# KIM_6530_replacement.net
KiCad netlist of a schematic drawn in EAGLE
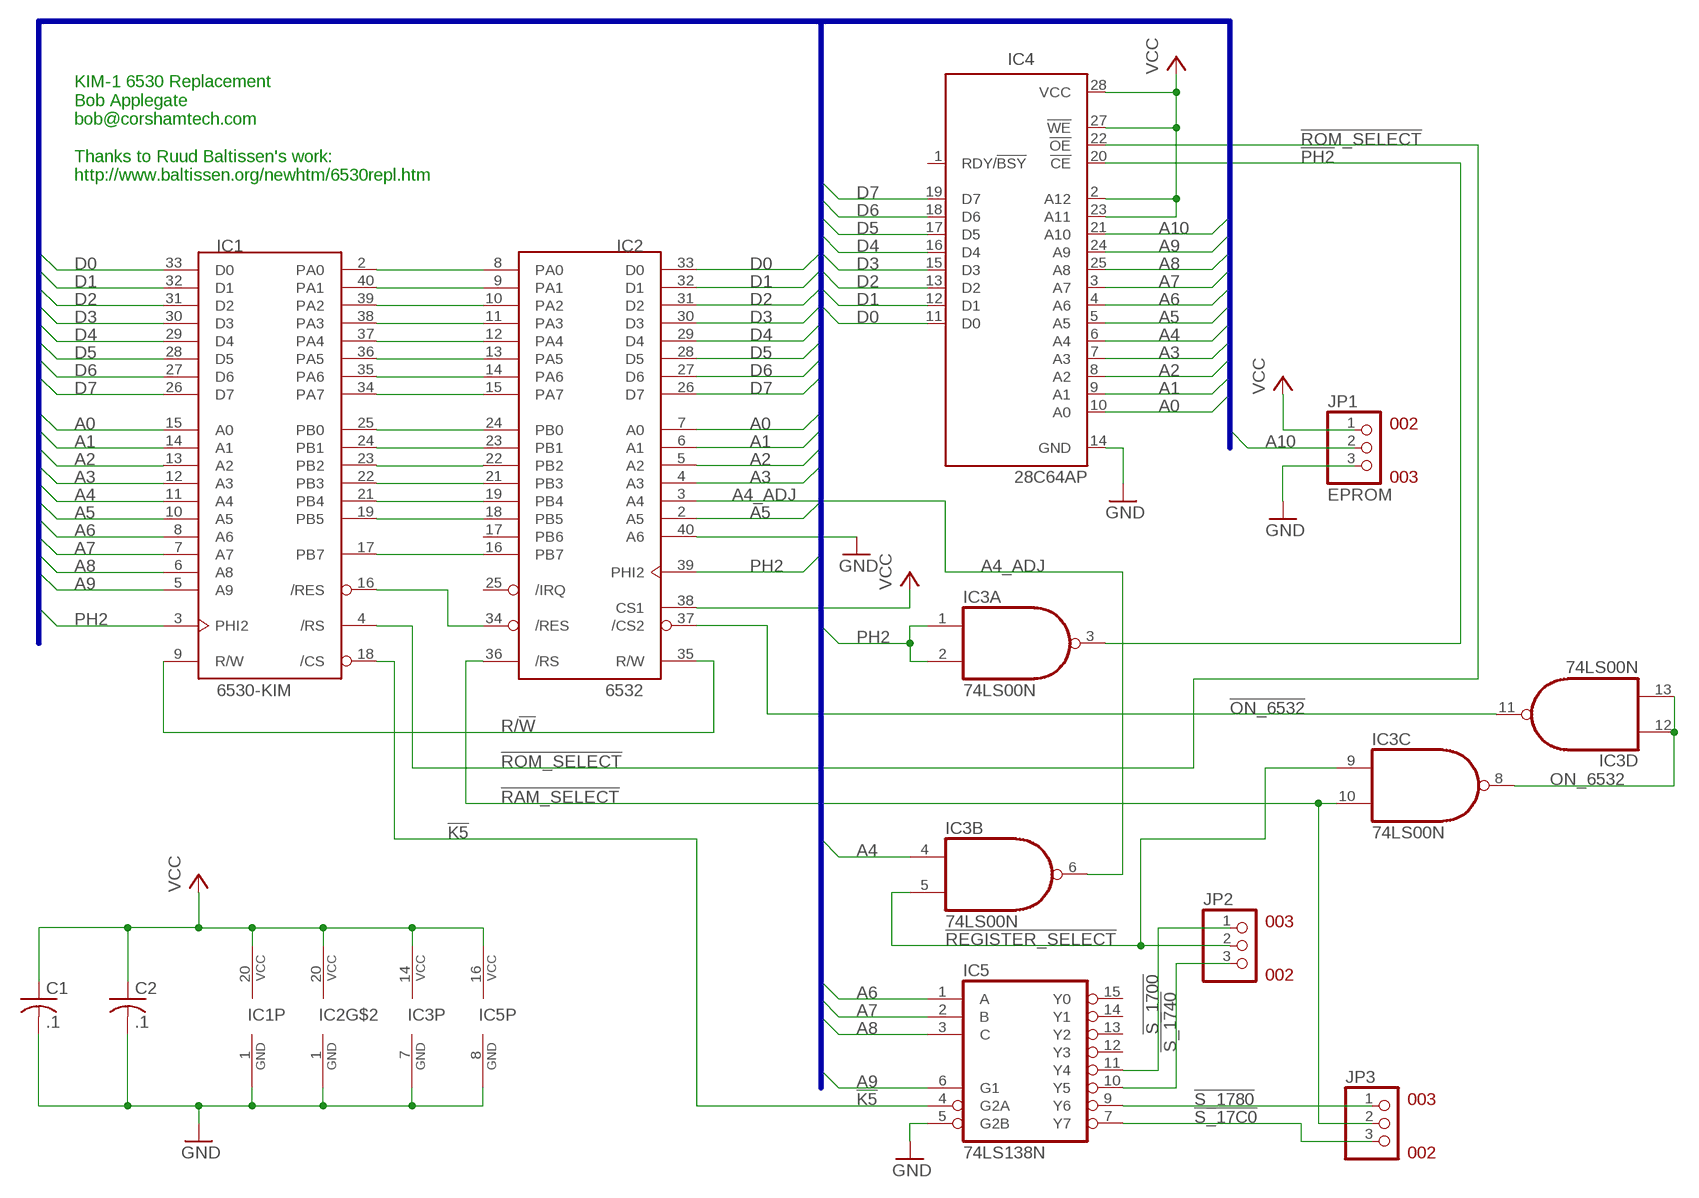
[diagram p0: schematic, sheet 1]

(export (version "E")
  (design (tool "Eeschema 10.0.6"))
  (components
    (comp (ref "C1")
      (value ".1")
      (footprint "eagle-import:C025-025X050")
      (libsource (lib "eagle-import") (part "C-US025-025X050"))
    )
    (comp (ref "C2")
      (value ".1")
      (footprint "eagle-import:C025-025X050")
      (libsource (lib "eagle-import") (part "C-US025-025X050"))
    )
    (comp (ref "IC1")
      (value "6530-KIM")
      (footprint "eagle-import:DIP40")
      (libsource (lib "eagle-import") (part "6530-KIM"))
    )
    (comp (ref "IC2")
      (value "6532")
      (footprint "eagle-import:DIP40")
      (libsource (lib "eagle-import") (part "6532"))
    )
    (comp (ref "IC3")
      (value "74LS00N")
      (footprint "eagle-import:DIL14")
      (libsource (lib "eagle-import") (part "7400NLS"))
    )
    (comp (ref "IC4")
      (value "28C64AP")
      (footprint "eagle-import:DIL28-6")
      (fields (field (name "MPN") "AT28C64B-15PU"))
      (libsource (lib "eagle-import") (part "2864APC"))
    )
    (comp (ref "IC5")
      (value "74LS138N")
      (footprint "eagle-import:DIL16")
      (libsource (lib "eagle-import") (part "74138NLS"))
    )
    (comp (ref "JP1")
      (value "EPROM")
      (footprint "eagle-import:1X03")
      (libsource (lib "eagle-import") (part "PINHD-1X3"))
    )
    (comp (ref "JP2")
      (value "PINHD-1X3")
      (footprint "eagle-import:1X03")
      (libsource (lib "eagle-import") (part "PINHD-1X3"))
    )
    (comp (ref "JP3")
      (value "PINHD-1X3")
      (footprint "eagle-import:1X03")
      (libsource (lib "eagle-import") (part "PINHD-1X3"))
    )
  )
  (nets
    (net (code "1") (name "/A0") (class "Default")
      (node (ref "IC1") (pin "15") (pinfunction "A0_15") (pintype "input"))
      (node (ref "IC2") (pin "7") (pinfunction "A0_7") (pintype "input"))
      (node (ref "IC4") (pin "10") (pinfunction "A0_10") (pintype "input"))
    )
    (net (code "2") (name "/A1") (class "Default")
      (node (ref "IC1") (pin "14") (pinfunction "A1_14") (pintype "input"))
      (node (ref "IC2") (pin "6") (pinfunction "A1_6") (pintype "input"))
      (node (ref "IC4") (pin "9") (pinfunction "A1_9") (pintype "input"))
    )
    (net (code "3") (name "/A2") (class "Default")
      (node (ref "IC1") (pin "13") (pinfunction "A2_13") (pintype "input"))
      (node (ref "IC2") (pin "5") (pinfunction "A2_5") (pintype "input"))
      (node (ref "IC4") (pin "8") (pinfunction "A2_8") (pintype "input"))
    )
    (net (code "4") (name "/A3") (class "Default")
      (node (ref "IC1") (pin "12") (pinfunction "A3_12") (pintype "input"))
      (node (ref "IC2") (pin "4") (pinfunction "A3_4") (pintype "input"))
      (node (ref "IC4") (pin "7") (pinfunction "A3_7") (pintype "input"))
    )
    (net (code "5") (name "/A4") (class "Default")
      (node (ref "IC1") (pin "11") (pinfunction "A4_11") (pintype "input"))
      (node (ref "IC3") (pin "4") (pinfunction "I0_4") (pintype "input"))
      (node (ref "IC4") (pin "6") (pinfunction "A4_6") (pintype "input"))
    )
    (net (code "6") (name "/A4_ADJ") (class "Default")
      (node (ref "IC2") (pin "3") (pinfunction "A4_3") (pintype "input"))
      (node (ref "IC3") (pin "6") (pinfunction "O_6") (pintype "output"))
    )
    (net (code "7") (name "/A5") (class "Default")
      (node (ref "IC1") (pin "10") (pinfunction "A5_10") (pintype "input"))
      (node (ref "IC2") (pin "2") (pinfunction "A5_2") (pintype "input"))
      (node (ref "IC4") (pin "5") (pinfunction "A5_5") (pintype "input"))
    )
    (net (code "8") (name "/A6") (class "Default")
      (node (ref "IC1") (pin "8") (pinfunction "A6_8") (pintype "input"))
      (node (ref "IC4") (pin "4") (pinfunction "A6_4") (pintype "input"))
      (node (ref "IC5") (pin "1") (pinfunction "A_1") (pintype "input"))
    )
    (net (code "9") (name "/A7") (class "Default")
      (node (ref "IC1") (pin "7") (pinfunction "A7_7") (pintype "input"))
      (node (ref "IC4") (pin "3") (pinfunction "A7_3") (pintype "input"))
      (node (ref "IC5") (pin "2") (pinfunction "B_2") (pintype "input"))
    )
    (net (code "10") (name "/A8") (class "Default")
      (node (ref "IC1") (pin "6") (pinfunction "A8_6") (pintype "input"))
      (node (ref "IC4") (pin "25") (pinfunction "A8_25") (pintype "input"))
      (node (ref "IC5") (pin "3") (pinfunction "C_3") (pintype "input"))
    )
    (net (code "11") (name "/A9") (class "Default")
      (node (ref "IC1") (pin "5") (pinfunction "A9_5") (pintype "input"))
      (node (ref "IC4") (pin "24") (pinfunction "A9_24") (pintype "input"))
      (node (ref "IC5") (pin "6") (pinfunction "G1_6") (pintype "input"))
    )
    (net (code "12") (name "/A10") (class "Default")
      (node (ref "IC4") (pin "21") (pinfunction "A10_21") (pintype "input"))
      (node (ref "JP1") (pin "2") (pinfunction "2_2") (pintype "passive"))
    )
    (net (code "13") (name "/D0") (class "Default")
      (node (ref "IC1") (pin "33") (pinfunction "D0_33") (pintype "bidirectional"))
      (node (ref "IC2") (pin "33") (pinfunction "D0_33") (pintype "bidirectional"))
      (node (ref "IC4") (pin "11") (pinfunction "D0_11") (pintype "tri_state"))
    )
    (net (code "14") (name "/D1") (class "Default")
      (node (ref "IC1") (pin "32") (pinfunction "D1_32") (pintype "bidirectional"))
      (node (ref "IC2") (pin "32") (pinfunction "D1_32") (pintype "bidirectional"))
      (node (ref "IC4") (pin "12") (pinfunction "D1_12") (pintype "tri_state"))
    )
    (net (code "15") (name "/D2") (class "Default")
      (node (ref "IC1") (pin "31") (pinfunction "D2_31") (pintype "bidirectional"))
      (node (ref "IC2") (pin "31") (pinfunction "D2_31") (pintype "bidirectional"))
      (node (ref "IC4") (pin "13") (pinfunction "D2_13") (pintype "tri_state"))
    )
    (net (code "16") (name "/D3") (class "Default")
      (node (ref "IC1") (pin "30") (pinfunction "D3_30") (pintype "bidirectional"))
      (node (ref "IC2") (pin "30") (pinfunction "D3_30") (pintype "bidirectional"))
      (node (ref "IC4") (pin "15") (pinfunction "D3_15") (pintype "tri_state"))
    )
    (net (code "17") (name "/D4") (class "Default")
      (node (ref "IC1") (pin "29") (pinfunction "D4_29") (pintype "bidirectional"))
      (node (ref "IC2") (pin "29") (pinfunction "D4_29") (pintype "bidirectional"))
      (node (ref "IC4") (pin "16") (pinfunction "D4_16") (pintype "tri_state"))
    )
    (net (code "18") (name "/D5") (class "Default")
      (node (ref "IC1") (pin "28") (pinfunction "D5_28") (pintype "bidirectional"))
      (node (ref "IC2") (pin "28") (pinfunction "D5_28") (pintype "bidirectional"))
      (node (ref "IC4") (pin "17") (pinfunction "D5_17") (pintype "tri_state"))
    )
    (net (code "19") (name "/D6") (class "Default")
      (node (ref "IC1") (pin "27") (pinfunction "D6_27") (pintype "bidirectional"))
      (node (ref "IC2") (pin "27") (pinfunction "D6_27") (pintype "bidirectional"))
      (node (ref "IC4") (pin "18") (pinfunction "D6_18") (pintype "tri_state"))
    )
    (net (code "20") (name "/D7") (class "Default")
      (node (ref "IC1") (pin "26") (pinfunction "D7_26") (pintype "bidirectional"))
      (node (ref "IC2") (pin "26") (pinfunction "D7_26") (pintype "bidirectional"))
      (node (ref "IC4") (pin "19") (pinfunction "D7_19") (pintype "tri_state"))
    )
    (net (code "21") (name "/ON_6532") (class "Default")
      (node (ref "IC3") (pin "12") (pinfunction "I0_12") (pintype "input"))
      (node (ref "IC3") (pin "13") (pinfunction "I1_13") (pintype "input"))
      (node (ref "IC3") (pin "8") (pinfunction "O_8") (pintype "output"))
    )
    (net (code "22") (name "/PH2") (class "Default")
      (node (ref "IC1") (pin "3") (pinfunction "PHI2_3") (pintype "input"))
      (node (ref "IC2") (pin "39") (pinfunction "PHI2_39") (pintype "input"))
      (node (ref "IC3") (pin "1") (pinfunction "I0_1") (pintype "input"))
      (node (ref "IC3") (pin "2") (pinfunction "I1_2") (pintype "input"))
    )
    (net (code "23") (name "/R{slash}~{W}") (class "Default")
      (node (ref "IC1") (pin "9") (pinfunction "R/W_9") (pintype "input"))
      (node (ref "IC2") (pin "35") (pinfunction "R/W_35") (pintype "input"))
    )
    (net (code "24") (name "/~{K5}") (class "Default")
      (node (ref "IC1") (pin "18") (pinfunction "/CS_18") (pintype "input"))
      (node (ref "IC5") (pin "4") (pinfunction "G2A_4") (pintype "input"))
    )
    (net (code "25") (name "/~{ON_6532}") (class "Default")
      (node (ref "IC2") (pin "37") (pinfunction "/CS2_37") (pintype "input"))
      (node (ref "IC3") (pin "11") (pinfunction "O_11") (pintype "output"))
    )
    (net (code "26") (name "/~{PH2}") (class "Default")
      (node (ref "IC3") (pin "3") (pinfunction "O_3") (pintype "output"))
      (node (ref "IC4") (pin "20") (pinfunction "~{CE}_20") (pintype "input"))
    )
    (net (code "27") (name "/~{RAM_SELECT}") (class "Default")
      (node (ref "IC2") (pin "36") (pinfunction "/RS_36") (pintype "input"))
      (node (ref "IC3") (pin "10") (pinfunction "I1_10") (pintype "input"))
      (node (ref "JP3") (pin "2") (pinfunction "2_2") (pintype "passive"))
    )
    (net (code "28") (name "/~{REGISTER_SELECT}") (class "Default")
      (node (ref "IC3") (pin "5") (pinfunction "I1_5") (pintype "input"))
      (node (ref "IC3") (pin "9") (pinfunction "I0_9") (pintype "input"))
      (node (ref "JP2") (pin "2") (pinfunction "2_2") (pintype "passive"))
    )
    (net (code "29") (name "/~{ROM_SELECT}") (class "Default")
      (node (ref "IC1") (pin "4") (pinfunction "/RS_4") (pintype "input"))
      (node (ref "IC4") (pin "22") (pinfunction "~{OE}_22") (pintype "input"))
    )
    (net (code "30") (name "/~{S_17C0}") (class "Default")
      (node (ref "IC5") (pin "7") (pinfunction "Y7_7") (pintype "output"))
      (node (ref "JP3") (pin "3") (pinfunction "3_3") (pintype "passive"))
    )
    (net (code "31") (name "/~{S_1700}") (class "Default")
      (node (ref "IC5") (pin "11") (pinfunction "Y4_11") (pintype "output"))
      (node (ref "JP2") (pin "1") (pinfunction "1_1") (pintype "passive"))
    )
    (net (code "32") (name "/~{S_1740}") (class "Default")
      (node (ref "IC5") (pin "10") (pinfunction "Y5_10") (pintype "output"))
      (node (ref "JP2") (pin "3") (pinfunction "3_3") (pintype "passive"))
    )
    (net (code "33") (name "/~{S_1780}") (class "Default")
      (node (ref "IC5") (pin "9") (pinfunction "Y6_9") (pintype "output"))
      (node (ref "JP3") (pin "1") (pinfunction "1_1") (pintype "passive"))
    )
    (net (code "34") (name "GND") (class "Default")
      (node (ref "C1") (pin "2") (pinfunction "2_2") (pintype "passive"))
      (node (ref "C2") (pin "2") (pinfunction "2_2") (pintype "passive"))
      (node (ref "IC1") (pin "1") (pinfunction "GND_1") (pintype "power_in"))
      (node (ref "IC2") (pin "1") (pinfunction "GND_1") (pintype "power_in"))
      (node (ref "IC2") (pin "40") (pinfunction "A6_40") (pintype "input"))
      (node (ref "IC3") (pin "7") (pinfunction "GND_7") (pintype "power_in"))
      (node (ref "IC4") (pin "14") (pinfunction "GND_14") (pintype "power_in"))
      (node (ref "IC5") (pin "5") (pinfunction "G2B_5") (pintype "input"))
      (node (ref "IC5") (pin "8") (pinfunction "GND_8") (pintype "power_in"))
      (node (ref "JP1") (pin "3") (pinfunction "3_3") (pintype "passive"))
    )
    (net (code "35") (name "Net-(IC1A-PA0)") (class "Default")
      (node (ref "IC1") (pin "2") (pinfunction "PA0_2") (pintype "bidirectional"))
      (node (ref "IC2") (pin "8") (pinfunction "PA0_8") (pintype "bidirectional"))
    )
    (net (code "36") (name "Net-(IC1A-PA1)") (class "Default")
      (node (ref "IC1") (pin "40") (pinfunction "PA1_40") (pintype "bidirectional"))
      (node (ref "IC2") (pin "9") (pinfunction "PA1_9") (pintype "bidirectional"))
    )
    (net (code "37") (name "Net-(IC1A-PA2)") (class "Default")
      (node (ref "IC1") (pin "39") (pinfunction "PA2_39") (pintype "bidirectional"))
      (node (ref "IC2") (pin "10") (pinfunction "PA2_10") (pintype "bidirectional"))
    )
    (net (code "38") (name "Net-(IC1A-PA3)") (class "Default")
      (node (ref "IC1") (pin "38") (pinfunction "PA3_38") (pintype "bidirectional"))
      (node (ref "IC2") (pin "11") (pinfunction "PA3_11") (pintype "bidirectional"))
    )
    (net (code "39") (name "Net-(IC1A-PA4)") (class "Default")
      (node (ref "IC1") (pin "37") (pinfunction "PA4_37") (pintype "bidirectional"))
      (node (ref "IC2") (pin "12") (pinfunction "PA4_12") (pintype "bidirectional"))
    )
    (net (code "40") (name "Net-(IC1A-PA5)") (class "Default")
      (node (ref "IC1") (pin "36") (pinfunction "PA5_36") (pintype "bidirectional"))
      (node (ref "IC2") (pin "13") (pinfunction "PA5_13") (pintype "bidirectional"))
    )
    (net (code "41") (name "Net-(IC1A-PA6)") (class "Default")
      (node (ref "IC1") (pin "35") (pinfunction "PA6_35") (pintype "bidirectional"))
      (node (ref "IC2") (pin "14") (pinfunction "PA6_14") (pintype "bidirectional"))
    )
    (net (code "42") (name "Net-(IC1A-PA7)") (class "Default")
      (node (ref "IC1") (pin "34") (pinfunction "PA7_34") (pintype "bidirectional"))
      (node (ref "IC2") (pin "15") (pinfunction "PA7_15") (pintype "bidirectional"))
    )
    (net (code "43") (name "Net-(IC1A-PB0)") (class "Default")
      (node (ref "IC1") (pin "25") (pinfunction "PB0_25") (pintype "bidirectional"))
      (node (ref "IC2") (pin "24") (pinfunction "PB0_24") (pintype "bidirectional"))
    )
    (net (code "44") (name "Net-(IC1A-PB1)") (class "Default")
      (node (ref "IC1") (pin "24") (pinfunction "PB1_24") (pintype "bidirectional"))
      (node (ref "IC2") (pin "23") (pinfunction "PB1_23") (pintype "bidirectional"))
    )
    (net (code "45") (name "Net-(IC1A-PB2)") (class "Default")
      (node (ref "IC1") (pin "23") (pinfunction "PB2_23") (pintype "bidirectional"))
      (node (ref "IC2") (pin "22") (pinfunction "PB2_22") (pintype "bidirectional"))
    )
    (net (code "46") (name "Net-(IC1A-PB3)") (class "Default")
      (node (ref "IC1") (pin "22") (pinfunction "PB3_22") (pintype "bidirectional"))
      (node (ref "IC2") (pin "21") (pinfunction "PB3_21") (pintype "bidirectional"))
    )
    (net (code "47") (name "Net-(IC1A-PB4)") (class "Default")
      (node (ref "IC1") (pin "21") (pinfunction "PB4_21") (pintype "bidirectional"))
      (node (ref "IC2") (pin "19") (pinfunction "PB4_19") (pintype "bidirectional"))
    )
    (net (code "48") (name "Net-(IC1A-PB5)") (class "Default")
      (node (ref "IC1") (pin "19") (pinfunction "PB5_19") (pintype "bidirectional"))
      (node (ref "IC2") (pin "18") (pinfunction "PB5_18") (pintype "bidirectional"))
    )
    (net (code "49") (name "Net-(IC1A-PB7)") (class "Default")
      (node (ref "IC1") (pin "17") (pinfunction "PB7_17") (pintype "bidirectional"))
      (node (ref "IC2") (pin "16") (pinfunction "PB7_16") (pintype "bidirectional"))
    )
    (net (code "50") (name "Net-(IC1A-{slash}RES)") (class "Default")
      (node (ref "IC1") (pin "16") (pinfunction "/RES_16") (pintype "input"))
      (node (ref "IC2") (pin "34") (pinfunction "/RES_34") (pintype "input"))
    )
    (net (code "51") (name "VCC") (class "Default")
      (node (ref "C1") (pin "1") (pinfunction "1_1") (pintype "passive"))
      (node (ref "C2") (pin "1") (pinfunction "1_1") (pintype "passive"))
      (node (ref "IC1") (pin "20") (pinfunction "VCC_20") (pintype "power_in"))
      (node (ref "IC2") (pin "20") (pinfunction "VCC_20") (pintype "power_in"))
      (node (ref "IC2") (pin "38") (pinfunction "CS1_38") (pintype "input"))
      (node (ref "IC3") (pin "14") (pinfunction "VCC_14") (pintype "power_in"))
      (node (ref "IC4") (pin "2") (pinfunction "A12_2") (pintype "input"))
      (node (ref "IC4") (pin "23") (pinfunction "A11_23") (pintype "input"))
      (node (ref "IC4") (pin "27") (pinfunction "~{WE}_27") (pintype "input"))
      (node (ref "IC4") (pin "28") (pinfunction "VCC_28") (pintype "power_in"))
      (node (ref "IC5") (pin "16") (pinfunction "VCC_16") (pintype "power_in"))
      (node (ref "JP1") (pin "1") (pinfunction "1_1") (pintype "passive"))
    )
    (net (code "52") (name "unconnected-(IC2A-PB6-Pad17)") (class "Default")
      (node (ref "IC2") (pin "17") (pinfunction "PB6_17") (pintype "bidirectional"))
    )
    (net (code "53") (name "unconnected-(IC2A-{slash}IRQ-Pad25)") (class "Default")
      (node (ref "IC2") (pin "25") (pinfunction "/IRQ_25") (pintype "open_collector"))
    )
    (net (code "54") (name "unconnected-(IC4-RDY{slash}~{BSY}-Pad1)") (class "Default")
      (node (ref "IC4") (pin "1") (pinfunction "RDY/~{BSY}_1") (pintype "output"))
    )
    (net (code "55") (name "unconnected-(IC5A-Y0-Pad15)") (class "Default")
      (node (ref "IC5") (pin "15") (pinfunction "Y0_15") (pintype "output"))
    )
    (net (code "56") (name "unconnected-(IC5A-Y1-Pad14)") (class "Default")
      (node (ref "IC5") (pin "14") (pinfunction "Y1_14") (pintype "output"))
    )
    (net (code "57") (name "unconnected-(IC5A-Y2-Pad13)") (class "Default")
      (node (ref "IC5") (pin "13") (pinfunction "Y2_13") (pintype "output"))
    )
    (net (code "58") (name "unconnected-(IC5A-Y3-Pad12)") (class "Default")
      (node (ref "IC5") (pin "12") (pinfunction "Y3_12") (pintype "output"))
    )
  )
)
